# Main_Power_Supply.net
KiCad netlist of a schematic drawn in Altium Designer
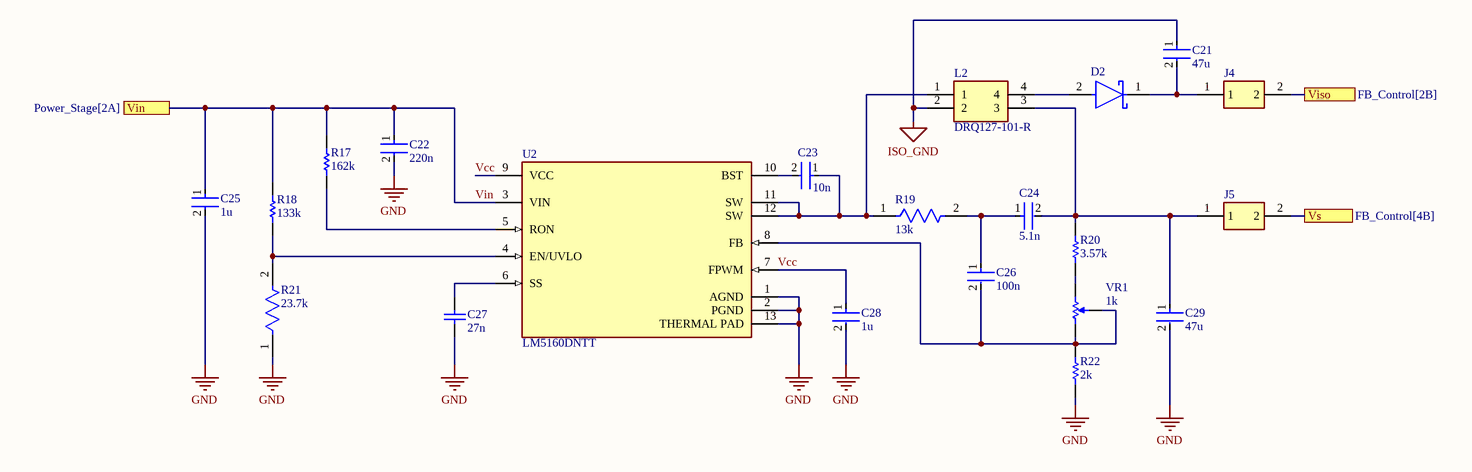
[diagram p0: Main_Power_Supply.SchDoc]

(export (version "E")
  (design (tool "Eeschema 10.0.6"))
  (components
    (comp (ref "C21")
      (value "47u")
      (footprint "FP-GRM32E-0_3-0_2-IPC_A")
      (description "Chip Multilayer Ceramic Capacitors for General Purpose, 1210, 47uF, X6S, 22%, 10%, 16V")
      (fields (field (name "TOLERANCE") "10%"))
      (libsource (lib "Altium Content Vault") (part "02cd4be3c70576c341d710602a673aa"))
    )
    (comp (ref "C22")
      (value "220n")
      (footprint "FP-GRM21A-0_1-MFG")
      (description "CAP CER 0.22UF 100V X7R 0805")
      (fields (field (name "VOLTAGE") "100V") (field (name "TOLERANCE") "10%"))
      (libsource (lib "Altium Content Vault") (part "02cd4be3c70576c341d710602a673aa"))
    )
    (comp (ref "C23")
      (value "10n")
      (footprint "FP-0805-L_2_01_0_2-W_1_25-IPC_B")
      (description "General Purpose Ceramic Capacitor, 0805, 10nF, 5%, X7R, 0.15, 50V")
      (fields (field (name "VOLTAGE") "50V") (field (name "TOLERANCE") "5%"))
      (libsource (lib "Altium Content Vault") (part "02cd4be3c70576c341d710602a673aa"))
    )
    (comp (ref "C24")
      (value "5.1n")
      (footprint "FP-GRM219-0_1-IPC_A")
      (description "Chip Multilayer Ceramic Capacitors for General Purpose, 0805, 5100pF, C0G, 30ppm/°C, 5%, 50V")
      (fields (field (name "VOLTAGE") "50V") (field (name "TOLERANCE") "5%"))
      (libsource (lib "Altium Content Vault") (part "02cd4be3c70576c341d710602a673aa"))
    )
    (comp (ref "C25")
      (value "1u")
      (footprint "FP-1210-L_3_3_0_4-W_2_5_0-IPC_C")
      (description "General Purpose Ceramic Capacitor, 1210, 1uF, 10%, X7R, 15%, 100V")
      (fields (field (name "TOLERANCE") "20%") (field (name "VOLTAGE") "100V"))
      (libsource (lib "Altium Content Vault") (part "b4654b650e69147ec39a6b967a45e02"))
    )
    (comp (ref "C26")
      (value "100n")
      (footprint "FP-0805-L_2_01_0_2-W_1_25-MFG")
      (description "General Purpose Ceramic Capacitor, 0805, 100nF, 5%, X7R, 0.15, 50V")
      (fields (field (name "TOLERANCE") "5%") (field (name "VOLTAGE") "50V"))
      (libsource (lib "Altium Content Vault") (part "02cd4be3c70576c341d710602a673aa"))
    )
    (comp (ref "C27")
      (value "27n")
      (footprint "CAPC1005X56X25LL10T15")
      (fields
        (field (name "PART NUMBER") "0402YD273KAT2A")
        (field (name "MANUFACTURER") "AVX Interconnect / Elco")
      )
      (libsource (lib "Altium Content Vault") (part "CAP"))
    )
    (comp (ref "C28")
      (value "1u")
      (footprint "FP-1210-L_3_3_0_4-W_2_5_0-IPC_C")
      (description "General Purpose Ceramic Capacitor, 1210, 1uF, 10%, X7R, 15%, 100V")
      (fields (field (name "TOLERANCE") "20%") (field (name "VOLTAGE") "100V"))
      (libsource (lib "Altium Content Vault") (part "b4654b650e69147ec39a6b967a45e02"))
    )
    (comp (ref "C29")
      (value "47u")
      (footprint "FP-GRM32E-0_3-0_2-IPC_A")
      (description "Chip Multilayer Ceramic Capacitors for General Purpose, 1210, 47uF, X6S, 22%, 10%, 16V")
      (fields (field (name "TOLERANCE") "10%"))
      (libsource (lib "Altium Content Vault") (part "02cd4be3c70576c341d710602a673aa"))
    )
    (comp (ref "D2")
      (value "MBR230LSFT1G")
      (footprint "FP-498-MFG")
      (description "DIODE SCHOTTKY 30V 2A SOD123L")
      (libsource (lib "Altium Content Vault") (part "1d6ec82d83fb6aee721767c19dac4b9"))
    )
    (comp (ref "J4")
      (value "22-28-4020")
      (footprint "Library:MOLEX_22-28-4020")
      (description "Connector Header Through Hole 2 position 0.100 (2.54mm)")
      (fields (field (name "MF") "Molex"))
      (libsource (lib "Library") (part "22-28-4020"))
    )
    (comp (ref "J5")
      (value "22-28-4020")
      (footprint "Library:MOLEX_22-28-4020")
      (description "Connector Header Through Hole 2 position 0.100 (2.54mm)")
      (fields (field (name "MF") "Molex"))
      (libsource (lib "Library") (part "22-28-4020"))
    )
    (comp (ref "L2")
      (value "DRQ127-101-R")
      (footprint "Library:DRQ127101R")
      (description "Inductor")
      (fields (field (name "MOUSER PART NUMBER") "704-DRQ127-101-R"))
      (libsource (lib "*") (part "DRQ127-101-R"))
    )
    (comp (ref "R17")
      (value "162k")
      (footprint "RESC1608X55X30ML15T15")
      (fields (field (name "MANUFACTURER") "Panasonic") (field (name "PART NUMBER") "ERJ-3EKF1623V"))
      (libsource (lib "Altium Content Vault") (part "RES"))
    )
    (comp (ref "R18")
      (value "133k")
      (footprint "RESC1608X55X30LL15T15")
      (fields (field (name "MANUFACTURER") "Panasonic") (field (name "PART NUMBER") "ERJ-3EKF1333V"))
      (libsource (lib "Altium Content Vault") (part "RES"))
    )
    (comp (ref "R19")
      (value "13k")
      (footprint "FP-ERJ3EK-IPC_C")
      (description "RES SMD 13K OHM 1% 1/10W 0603")
      (fields (field (name "TOLERANCE") "1%"))
      (libsource (lib "Altium Content Vault") (part "1029c3af85768c4190bb7ad29bc67b5"))
    )
    (comp (ref "R20")
      (value "3.57k")
      (footprint "RESC1608X55X30LL15T15")
      (fields (field (name "PART NUMBER") "ERJ-3EKF3571V") (field (name "MANUFACTURER") "Panasonic"))
      (libsource (lib "Altium Content Vault") (part "RES"))
    )
    (comp (ref "R21")
      (value "23.7k")
      (footprint "FP-ERJ3EK-IPC_C")
      (description "RES SMD 23.7K OHM 1% 1/10W 0603")
      (fields (field (name "TOLERANCE") "1%"))
      (libsource (lib "Altium Content Vault") (part "1029c3af85768c4190bb7ad29bc67b5"))
    )
    (comp (ref "R22")
      (value "2k")
      (footprint "RESC1608X55X30ML15T15")
      (fields (field (name "PART NUMBER") "ERJ-3EKF2001V") (field (name "MANUFACTURER") "Panasonic"))
      (libsource (lib "Altium Content Vault") (part "RES"))
    )
    (comp (ref "U2")
      (value "LM5160DNTT")
      (footprint "FP-DNT0012B-MFG")
      (description "IC REG BCK FLYBCK ADJ 12WSON")
      (libsource (lib "Altium Content Vault") (part "1d7f67e77d13906a14c82768b36e50a"))
    )
    (comp (ref "VR1")
      (value "1k")
      (footprint "BOUR-3296W-1-3")
      (description "Square Trimpot(R) Trimming Potentiometer, 1000 Ohm, -55 to 125 degC, 3-Pin THD, RoHS, Tube")
      (fields (field (name "TOLERANCE") "1%"))
      (libsource (lib "Altium Content Vault") (part "RES-ADJ-3"))
    )
  )
  (nets
    (net (code "1") (name "/Vcc") (class "Default")
      (node (ref "C28") (pin "1") (pinfunction "1_1") (pintype "passive"))
      (node (ref "U2") (pin "7") (pinfunction "FPWM_7") (pintype "input"))
      (node (ref "U2") (pin "9") (pinfunction "VCC_9") (pintype "power_in"))
    )
    (net (code "2") (name "/Vin") (class "Default")
      (node (ref "C22") (pin "1") (pinfunction "1_1") (pintype "passive"))
      (node (ref "C25") (pin "1") (pinfunction "1_1") (pintype "passive"))
      (node (ref "R17") (pin "2") (pinfunction "2_2") (pintype "passive"))
      (node (ref "R18") (pin "2") (pinfunction "2_2") (pintype "passive"))
      (node (ref "U2") (pin "3") (pinfunction "VIN_3") (pintype "power_in"))
    )
    (net (code "3") (name "/Viso") (class "Default")
      (node (ref "J4") (pin "2") (pinfunction "2_2") (pintype "passive"))
    )
    (net (code "4") (name "/Vs") (class "Default")
      (node (ref "J5") (pin "2") (pinfunction "2_2") (pintype "passive"))
    )
    (net (code "5") (name "GND") (class "Default")
      (node (ref "C22") (pin "2") (pinfunction "2_2") (pintype "passive"))
      (node (ref "C25") (pin "2") (pinfunction "2_2") (pintype "passive"))
      (node (ref "C27") (pin "1") (pinfunction "1_1") (pintype "passive"))
      (node (ref "C28") (pin "2") (pinfunction "2_2") (pintype "passive"))
      (node (ref "C29") (pin "2") (pinfunction "2_2") (pintype "passive"))
      (node (ref "R21") (pin "1") (pinfunction "1_1") (pintype "passive"))
      (node (ref "R22") (pin "1") (pinfunction "1_1") (pintype "passive"))
      (node (ref "U2") (pin "1") (pinfunction "AGND_1") (pintype "power_in"))
      (node (ref "U2") (pin "13") (pinfunction "THERMAL_PAD_13") (pintype "power_in"))
      (node (ref "U2") (pin "2") (pinfunction "PGND_2") (pintype "power_in"))
    )
    (net (code "6") (name "ISO_GND") (class "Default")
      (node (ref "C21") (pin "1") (pinfunction "1_1") (pintype "passive"))
      (node (ref "L2") (pin "2") (pinfunction "2_2") (pintype "passive"))
    )
    (net (code "7") (name "Net-(C23-Pad1)") (class "Default")
      (node (ref "C23") (pin "1") (pinfunction "1_1") (pintype "passive"))
      (node (ref "L2") (pin "1") (pinfunction "1_1") (pintype "passive"))
      (node (ref "R19") (pin "1") (pinfunction "1_1") (pintype "passive"))
      (node (ref "U2") (pin "11") (pinfunction "SW_11") (pintype "passive"))
      (node (ref "U2") (pin "12") (pinfunction "SW_12") (pintype "passive"))
    )
    (net (code "8") (name "Net-(C24-Pad1)") (class "Default")
      (node (ref "C24") (pin "1") (pinfunction "1_1") (pintype "passive"))
      (node (ref "C26") (pin "1") (pinfunction "1_1") (pintype "passive"))
      (node (ref "R19") (pin "2") (pinfunction "2_2") (pintype "passive"))
    )
    (net (code "9") (name "Net-(C24-Pad2)") (class "Default")
      (node (ref "C24") (pin "2") (pinfunction "2_2") (pintype "passive"))
      (node (ref "C29") (pin "1") (pinfunction "1_1") (pintype "passive"))
      (node (ref "J5") (pin "1") (pinfunction "1_1") (pintype "passive"))
      (node (ref "L2") (pin "3") (pinfunction "3_3") (pintype "passive"))
      (node (ref "R20") (pin "2") (pinfunction "2_2") (pintype "passive"))
    )
    (net (code "10") (name "Net-(D2-A)") (class "Default")
      (node (ref "D2") (pin "2") (pinfunction "A_2") (pintype "passive"))
      (node (ref "L2") (pin "4") (pinfunction "4_4") (pintype "passive"))
    )
    (net (code "11") (name "Net-(D2-C)") (class "Default")
      (node (ref "C21") (pin "2") (pinfunction "2_2") (pintype "passive"))
      (node (ref "D2") (pin "1") (pinfunction "C_1") (pintype "passive"))
      (node (ref "J4") (pin "1") (pinfunction "1_1") (pintype "passive"))
    )
    (net (code "12") (name "Net-(U2-BST)") (class "Default")
      (node (ref "C23") (pin "2") (pinfunction "2_2") (pintype "passive"))
      (node (ref "U2") (pin "10") (pinfunction "BST_10") (pintype "passive"))
    )
    (net (code "13") (name "Net-(U2-EN{slash}UVLO)") (class "Default")
      (node (ref "R18") (pin "1") (pinfunction "1_1") (pintype "passive"))
      (node (ref "R21") (pin "2") (pinfunction "2_2") (pintype "passive"))
      (node (ref "U2") (pin "4") (pinfunction "EN/UVLO_4") (pintype "input"))
    )
    (net (code "14") (name "Net-(U2-FB)") (class "Default")
      (node (ref "C26") (pin "2") (pinfunction "2_2") (pintype "passive"))
      (node (ref "R22") (pin "2") (pinfunction "2_2") (pintype "passive"))
      (node (ref "U2") (pin "8") (pinfunction "FB_8") (pintype "input"))
      (node (ref "VR1") (pin "1") (pinfunction "A_1") (pintype "passive"))
      (node (ref "VR1") (pin "3") (pinfunction "TAP_3") (pintype "passive"))
    )
    (net (code "15") (name "Net-(U2-RON)") (class "Default")
      (node (ref "R17") (pin "1") (pinfunction "1_1") (pintype "passive"))
      (node (ref "U2") (pin "5") (pinfunction "RON_5") (pintype "input"))
    )
    (net (code "16") (name "Net-(U2-SS)") (class "Default")
      (node (ref "C27") (pin "2") (pinfunction "2_2") (pintype "passive"))
      (node (ref "U2") (pin "6") (pinfunction "SS_6") (pintype "input"))
    )
    (net (code "17") (name "Net-(VR1-B)") (class "Default")
      (node (ref "R20") (pin "1") (pinfunction "1_1") (pintype "passive"))
      (node (ref "VR1") (pin "2") (pinfunction "B_2") (pintype "passive"))
    )
  )
)
